# Schematics.net
KiCad netlist of a schematic drawn in Altium Designer
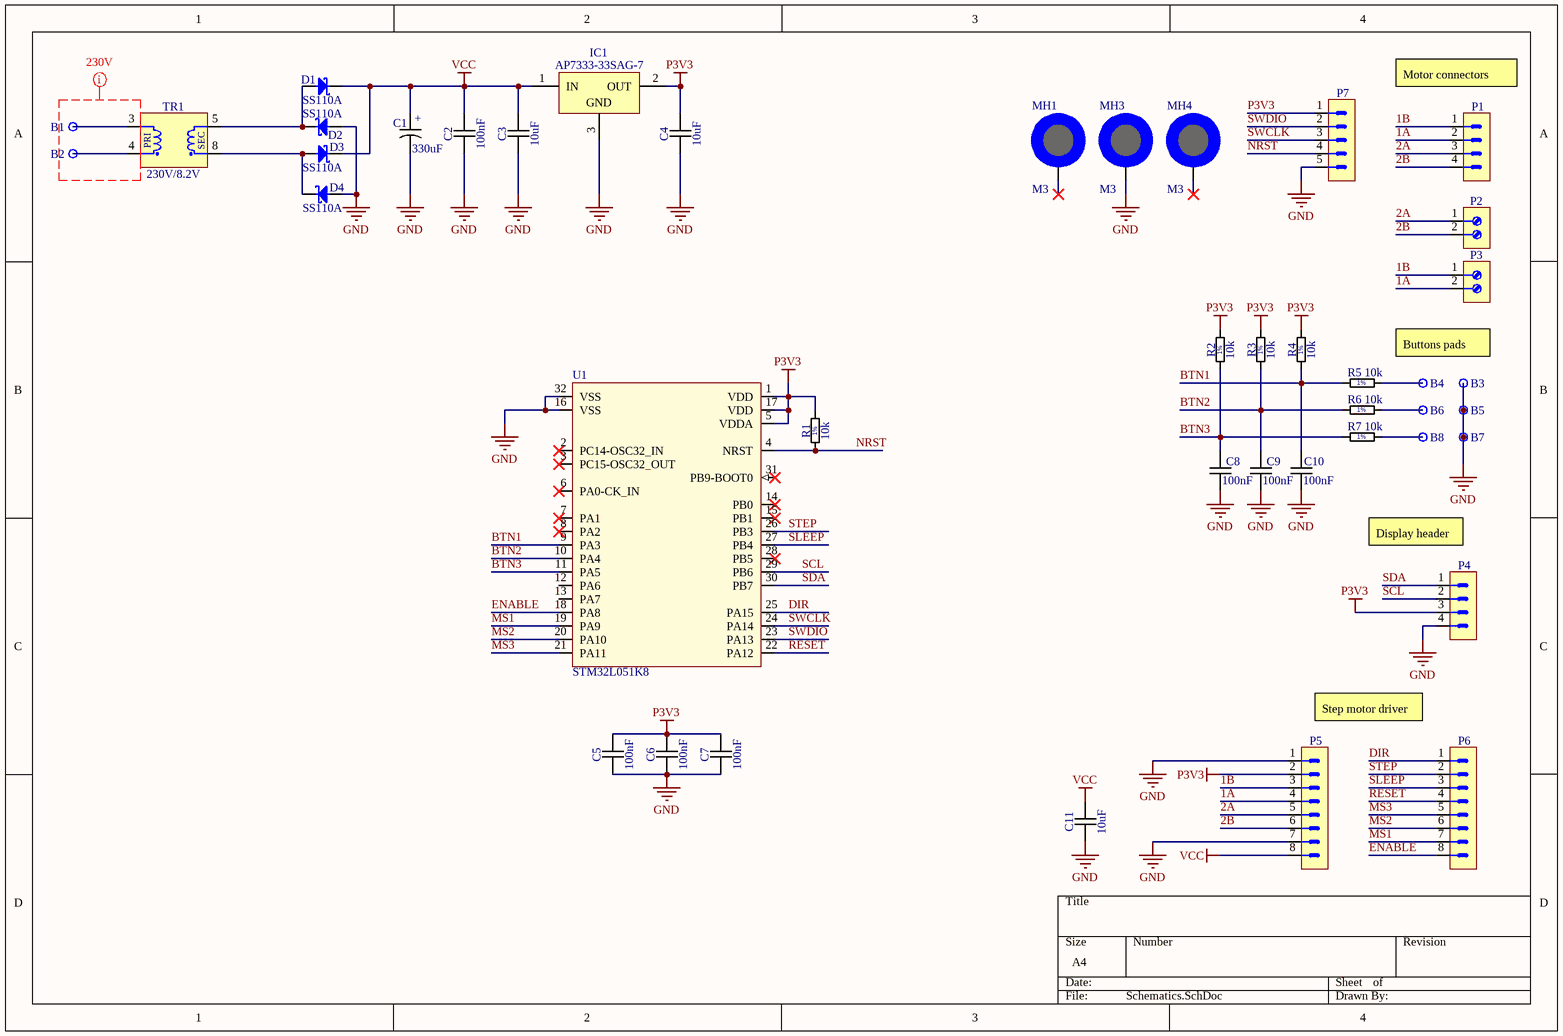
[diagram p0: Schematics.SchDoc]

(export (version "E")
  (design (tool "Eeschema 10.0.6"))
  (components
    (comp (ref "B1")
      (value "Pad")
      (footprint "PAD_THD_C350H200MM")
      (description "Plated Through Hole: Hole Dia.=2mm Pad Dia.=3.5mm")
      (fields (field (name "AUTHOR") "KB"))
      (libsource (lib "Mechanical And PCB Features") (part "THD Pad"))
    )
    (comp (ref "B2")
      (value "Pad")
      (footprint "PAD_THD_C350H200MM")
      (description "Plated Through Hole: Hole Dia.=2mm Pad Dia.=3.5mm")
      (fields (field (name "AUTHOR") "KB"))
      (libsource (lib "Mechanical And PCB Features") (part "THD Pad"))
    )
    (comp (ref "B3")
      (value "Pad")
      (footprint "PAD_THD_C150H100MM")
      (description "Plated Through Hole: Hole Dia.=1mm Pad Dia.=1.5mm")
      (fields (field (name "AUTHOR") "KB"))
      (libsource (lib "Mechanical And PCB Features") (part "THD Pad"))
    )
    (comp (ref "B4")
      (value "Pad")
      (footprint "PAD_THD_C150H100MM")
      (description "Plated Through Hole: Hole Dia.=1mm Pad Dia.=1.5mm")
      (fields (field (name "AUTHOR") "KB"))
      (libsource (lib "Mechanical And PCB Features") (part "THD Pad"))
    )
    (comp (ref "B5")
      (value "Pad")
      (footprint "PAD_THD_C150H100MM")
      (description "Plated Through Hole: Hole Dia.=1mm Pad Dia.=1.5mm")
      (fields (field (name "AUTHOR") "KB"))
      (libsource (lib "Mechanical And PCB Features") (part "THD Pad"))
    )
    (comp (ref "B6")
      (value "Pad")
      (footprint "PAD_THD_C150H100MM")
      (description "Plated Through Hole: Hole Dia.=1mm Pad Dia.=1.5mm")
      (fields (field (name "AUTHOR") "KB"))
      (libsource (lib "Mechanical And PCB Features") (part "THD Pad"))
    )
    (comp (ref "B7")
      (value "Pad")
      (footprint "PAD_THD_C150H100MM")
      (description "Plated Through Hole: Hole Dia.=1mm Pad Dia.=1.5mm")
      (fields (field (name "AUTHOR") "KB"))
      (libsource (lib "Mechanical And PCB Features") (part "THD Pad"))
    )
    (comp (ref "B8")
      (value "Pad")
      (footprint "PAD_THD_C150H100MM")
      (description "Plated Through Hole: Hole Dia.=1mm Pad Dia.=1.5mm")
      (fields (field (name "AUTHOR") "KB"))
      (libsource (lib "Mechanical And PCB Features") (part "THD Pad"))
    )
    (comp (ref "C1")
      (value "330uF")
      (footprint "CAPPR5-10x16")
      (description "Polarised capacitor")
      (fields
        (field (name "MANUFACTURER") "GENERIC")
        (field (name "MANUFACTURER PART NUMBER") "CE_THT_5-10X16_330UF_50V_20%")
        (field (name "AUTHOR") "UN")
      )
      (libsource (lib "Capacitors") (part "Capacitor - polarized"))
    )
    (comp (ref "C2")
      (value "100nF")
      (footprint "CAPC0603X90N")
      (description "Non-polarised capacitor")
      (fields
        (field (name "MANUFACTURER") "GENERIC")
        (field (name "MANUFACTURER PART NUMBER") "CC0603_100NF_16V_10%_X7R")
        (field (name "AUTHOR") "KB")
      )
      (libsource (lib "Capacitors") (part "Capacitor - non polarized"))
    )
    (comp (ref "C3")
      (value "10uF")
      (footprint "CAPC0603X90N")
      (description "Non-polarised capacitor")
      (fields
        (field (name "MANUFACTURER") "GENERIC")
        (field (name "MANUFACTURER PART NUMBER") "CC0603_10UF_16V_20%_X5R")
        (field (name "AUTHOR") "KB")
      )
      (libsource (lib "Capacitors") (part "Capacitor - non polarized"))
    )
    (comp (ref "C4")
      (value "10uF")
      (footprint "CAPC0603X90N")
      (description "Non-polarised capacitor")
      (fields
        (field (name "MANUFACTURER") "GENERIC")
        (field (name "MANUFACTURER PART NUMBER") "CC0603_10UF_16V_20%_X5R")
        (field (name "AUTHOR") "KB")
      )
      (libsource (lib "Capacitors") (part "Capacitor - non polarized"))
    )
    (comp (ref "C5")
      (value "100nF")
      (footprint "CAPC0603X90N")
      (description "Non-polarised capacitor")
      (fields
        (field (name "MANUFACTURER") "GENERIC")
        (field (name "MANUFACTURER PART NUMBER") "CC0603_100NF_16V_10%_X7R")
        (field (name "AUTHOR") "KB")
      )
      (libsource (lib "Capacitors") (part "Capacitor - non polarized"))
    )
    (comp (ref "C6")
      (value "100nF")
      (footprint "CAPC0603X90N")
      (description "Non-polarised capacitor")
      (fields
        (field (name "MANUFACTURER") "GENERIC")
        (field (name "MANUFACTURER PART NUMBER") "CC0603_100NF_16V_10%_X7R")
        (field (name "AUTHOR") "KB")
      )
      (libsource (lib "Capacitors") (part "Capacitor - non polarized"))
    )
    (comp (ref "C7")
      (value "100nF")
      (footprint "CAPC0603X90N")
      (description "Non-polarised capacitor")
      (fields
        (field (name "MANUFACTURER") "GENERIC")
        (field (name "MANUFACTURER PART NUMBER") "CC0603_100NF_16V_10%_X7R")
        (field (name "AUTHOR") "KB")
      )
      (libsource (lib "Capacitors") (part "Capacitor - non polarized"))
    )
    (comp (ref "C8")
      (value "100nF")
      (footprint "CAPC0603X90N")
      (description "Non-polarised capacitor")
      (fields
        (field (name "MANUFACTURER") "GENERIC")
        (field (name "MANUFACTURER PART NUMBER") "CC0603_100NF_16V_10%_X7R")
        (field (name "AUTHOR") "KB")
      )
      (libsource (lib "Capacitors") (part "Capacitor - non polarized"))
    )
    (comp (ref "C9")
      (value "100nF")
      (footprint "CAPC0603X90N")
      (description "Non-polarised capacitor")
      (fields
        (field (name "MANUFACTURER") "GENERIC")
        (field (name "MANUFACTURER PART NUMBER") "CC0603_100NF_16V_10%_X7R")
        (field (name "AUTHOR") "KB")
      )
      (libsource (lib "Capacitors") (part "Capacitor - non polarized"))
    )
    (comp (ref "C10")
      (value "100nF")
      (footprint "CAPC0603X90N")
      (description "Non-polarised capacitor")
      (fields
        (field (name "MANUFACTURER") "GENERIC")
        (field (name "MANUFACTURER PART NUMBER") "CC0603_100NF_16V_10%_X7R")
        (field (name "AUTHOR") "KB")
      )
      (libsource (lib "Capacitors") (part "Capacitor - non polarized"))
    )
    (comp (ref "C11")
      (value "10uF")
      (footprint "CAPC0603X90N")
      (description "Non-polarised capacitor")
      (fields
        (field (name "MANUFACTURER") "GENERIC")
        (field (name "MANUFACTURER PART NUMBER") "CC0603_10UF_16V_20%_X5R")
        (field (name "AUTHOR") "KB")
      )
      (libsource (lib "Capacitors") (part "Capacitor - non polarized"))
    )
    (comp (ref "D1")
      (value "SS110A")
      (footprint "DO-214AC - Schottky")
      (description "Surface Mount Schottky Rectifier")
      (fields (field (name "AUTHOR") "JK"))
      (libsource (lib "ICs And Semiconductors") (part "Diode Schottky"))
    )
    (comp (ref "D2")
      (value "SS110A")
      (footprint "DO-214AC - Schottky")
      (description "Surface Mount Schottky Rectifier")
      (fields (field (name "AUTHOR") "JK"))
      (libsource (lib "ICs And Semiconductors") (part "Diode Schottky"))
    )
    (comp (ref "D3")
      (value "SS110A")
      (footprint "DO-214AC - Schottky")
      (description "Surface Mount Schottky Rectifier")
      (fields (field (name "AUTHOR") "JK"))
      (libsource (lib "ICs And Semiconductors") (part "Diode Schottky"))
    )
    (comp (ref "D4")
      (value "SS110A")
      (footprint "DO-214AC - Schottky")
      (description "Surface Mount Schottky Rectifier")
      (fields (field (name "AUTHOR") "JK"))
      (libsource (lib "ICs And Semiconductors") (part "Diode Schottky"))
    )
    (comp (ref "IC1")
      (value "AP7333-33SAG-7")
      (footprint "SOT23-3")
      (description "3.3V, 0.3A output; Vin 6V max, 0.3V dropout")
      (fields (field (name "AUTHOR") "BS"))
      (libsource (lib "ICs And Semiconductors") (part "REG3 1IN-2OUT-3GND"))
    )
    (comp (ref "MH1")
      (value "M3")
      (footprint "MH-M3_COPPER_WASHER")
      (description "Mounting hole, M3, exposed pad, space for washer")
      (fields (field (name "AUTHOR") "KB"))
      (libsource (lib "Mechanical And PCB Features") (part "MH"))
    )
    (comp (ref "MH3")
      (value "M3")
      (footprint "MH-M3_COPPER_WASHER")
      (description "Mounting hole, M3, exposed pad, space for washer")
      (fields (field (name "AUTHOR") "KB"))
      (libsource (lib "Mechanical And PCB Features") (part "MH"))
    )
    (comp (ref "MH4")
      (value "M3")
      (footprint "MH-M3_COPPER_WASHER")
      (description "Mounting hole, M3, exposed pad, space for washer")
      (fields (field (name "AUTHOR") "KB"))
      (libsource (lib "Mechanical And PCB Features") (part "MH"))
    )
    (comp (ref "P1")
      (value "B4B-PH-K-S")
      (footprint "B4B-PH-K-S")
      (description "2mm header socket, vertical, 4 Positions, THT, 9.9x4.5mm body")
      (fields (field (name "MANUFACTURER") "GENERIC") (field (name "AUTHOR") "KB"))
      (libsource (lib "Connectors") (part "Header 4x1"))
    )
    (comp (ref "P2")
      (value "1776275")
      (footprint "SCREWERM_THT_2X1H_3P5MM")
      (description "Terminal Block, Right angle, 2 Positions, THT, Screw Connection, 7x7mm body")
      (fields
        (field (name "MANUFACTURER") "GENERIC")
        (field (name "MANUFACTURER PART NUMBER") "SCREWERM_THT_2X1H_3P5MM")
        (field (name "AUTHOR") "JK")
      )
      (libsource (lib "Connectors") (part "Terminal Block_2 Positions_Screw Connection"))
    )
    (comp (ref "P3")
      (value "1776275")
      (footprint "SCREWERM_THT_2X1H_3P5MM")
      (description "Terminal Block, Right angle, 2 Positions, THT, Screw Connection, 7x7mm body")
      (fields
        (field (name "MANUFACTURER") "GENERIC")
        (field (name "MANUFACTURER PART NUMBER") "SCREWERM_THT_2X1H_3P5MM")
        (field (name "AUTHOR") "JK")
      )
      (libsource (lib "Connectors") (part "Terminal Block_2 Positions_Screw Connection"))
    )
    (comp (ref "P4")
      (value "SSW-104-02-L-S")
      (footprint "SAMTEC_SSW-104-02-L-S")
      (description "General Purpose Header: THT, 2.54mm, Female, Straight")
      (fields
        (field (name "MANUFACTURER") "GENERIC")
        (field (name "MANUFACTURER PART NUMBER") "HDR_THT_4X1V_F_2P54MM")
        (field (name "AUTHOR") "PC")
      )
      (libsource (lib "Connectors") (part "Header 4x1"))
    )
    (comp (ref "P5")
      (value "68000-208HLF")
      (footprint "Header_8x1_V_2.54mm_M")
      (description "General Purpose Header: THT, 2.54mm, Male, Straight")
      (fields
        (field (name "MANUFACTURER") "GENERIC")
        (field (name "MANUFACTURER PART NUMBER") "Header_8x1_V_2.54mm_M")
        (field (name "AUTHOR") "JK")
      )
      (libsource (lib "Connectors") (part "Header 8x1"))
    )
    (comp (ref "P6")
      (value "68000-208HLF")
      (footprint "Header_8x1_V_2.54mm_M")
      (description "General Purpose Header: THT, 2.54mm, Male, Straight")
      (fields
        (field (name "MANUFACTURER") "GENERIC")
        (field (name "MANUFACTURER PART NUMBER") "Header_8x1_V_2.54mm_M")
        (field (name "AUTHOR") "JK")
      )
      (libsource (lib "Connectors") (part "Header 8x1"))
    )
    (comp (ref "P7")
      (value "SSW-105-02-G-S")
      (footprint "SAMTEC_SSW-105-02-G-S")
      (description "General Purpose Header: THT, 2.54mm, Female, Straight, Long Lead")
      (fields
        (field (name "MANUFACTURER") "GENERIC")
        (field (name "MANUFACTURER PART NUMBER") "HDR_THT_5X1V_F_2P54MM")
        (field (name "AUTHOR") "UN")
      )
      (libsource (lib "Connectors") (part "Header 5x1"))
    )
    (comp (ref "R1")
      (value "10k")
      (footprint "RESC0603X60N")
      (description "General Purpose Thick Film Chip Resistor")
      (fields
        (field (name "MANUFACTURER") "GENERIC")
        (field (name "MANUFACTURER PART NUMBER") "R0603_10K0_0.0625W 0.1W 0.125W 0.25W 0.5W 1W 0.75W 1W_100PPM")
        (field (name "AUTHOR") "KB")
      )
      (libsource (lib "Resistors") (part "Resistor - 1%"))
    )
    (comp (ref "R2")
      (value "10k")
      (footprint "RESC0603X60N")
      (description "General Purpose Thick Film Chip Resistor")
      (fields
        (field (name "MANUFACTURER") "GENERIC")
        (field (name "MANUFACTURER PART NUMBER") "R0603_10K0_0.0625W 0.1W 0.125W 0.25W 0.5W 1W 0.75W 1W_100PPM")
        (field (name "AUTHOR") "KB")
      )
      (libsource (lib "Resistors") (part "Resistor - 1%"))
    )
    (comp (ref "R3")
      (value "10k")
      (footprint "RESC0603X60N")
      (description "General Purpose Thick Film Chip Resistor")
      (fields
        (field (name "MANUFACTURER") "GENERIC")
        (field (name "MANUFACTURER PART NUMBER") "R0603_10K0_0.0625W 0.1W 0.125W 0.25W 0.5W 1W 0.75W 1W_100PPM")
        (field (name "AUTHOR") "KB")
      )
      (libsource (lib "Resistors") (part "Resistor - 1%"))
    )
    (comp (ref "R4")
      (value "10k")
      (footprint "RESC0603X60N")
      (description "General Purpose Thick Film Chip Resistor")
      (fields
        (field (name "MANUFACTURER") "GENERIC")
        (field (name "MANUFACTURER PART NUMBER") "R0603_10K0_0.0625W 0.1W 0.125W 0.25W 0.5W 1W 0.75W 1W_100PPM")
        (field (name "AUTHOR") "KB")
      )
      (libsource (lib "Resistors") (part "Resistor - 1%"))
    )
    (comp (ref "R5")
      (value "10k")
      (footprint "RESC0603X60N")
      (description "General Purpose Thick Film Chip Resistor")
      (fields
        (field (name "MANUFACTURER") "GENERIC")
        (field (name "MANUFACTURER PART NUMBER") "R0603_10K0_0.0625W 0.1W 0.125W 0.25W 0.5W 1W 0.75W 1W_100PPM")
        (field (name "AUTHOR") "KB")
      )
      (libsource (lib "Resistors") (part "Resistor - 1%"))
    )
    (comp (ref "R6")
      (value "10k")
      (footprint "RESC0603X60N")
      (description "General Purpose Thick Film Chip Resistor")
      (fields
        (field (name "MANUFACTURER") "GENERIC")
        (field (name "MANUFACTURER PART NUMBER") "R0603_10K0_0.0625W 0.1W 0.125W 0.25W 0.5W 1W 0.75W 1W_100PPM")
        (field (name "AUTHOR") "KB")
      )
      (libsource (lib "Resistors") (part "Resistor - 1%"))
    )
    (comp (ref "R7")
      (value "10k")
      (footprint "RESC0603X60N")
      (description "General Purpose Thick Film Chip Resistor")
      (fields
        (field (name "MANUFACTURER") "GENERIC")
        (field (name "MANUFACTURER PART NUMBER") "R0603_10K0_0.0625W 0.1W 0.125W 0.25W 0.5W 1W 0.75W 1W_100PPM")
        (field (name "AUTHOR") "KB")
      )
      (libsource (lib "Resistors") (part "Resistor - 1%"))
    )
    (comp (ref "TR1")
      (value "230V/8.2V")
      (footprint "TS 2/14")
      (description "Transformer")
      (fields
        (field (name "MANUFACTURER") "INDEL")
        (field (name "MANUFACTURER PART NUMBER") "TS 2/14")
        (field (name "AUTHOR") "JK")
      )
      (libsource (lib "Inductors") (part "TS 2/14"))
    )
    (comp (ref "U1")
      (value "STM32L051K8")
      (footprint "STM-LQFP32_N")
      (description "Ultra-low-power ARM Cortex-M0+ MCU with 64 Kbytes Flash, 32 MHz CPU")
      (fields (field (name "MANUFACTURER 1 PART NUMBER") "STM32L051K8T6") (field (name "AUTHOR") "JK"))
      (libsource (lib "ICs And Semiconductors") (part "STM32L051K8"))
    )
  )
  (nets
    (net (code "1") (name "/1A") (class "Default")
      (node (ref "P1") (pin "2") (pinfunction "2_2") (pintype "passive"))
      (node (ref "P3") (pin "2") (pinfunction "2_2") (pintype "passive"))
      (node (ref "P5") (pin "4") (pinfunction "4_4") (pintype "passive"))
    )
    (net (code "2") (name "/1B") (class "Default")
      (node (ref "P1") (pin "1") (pinfunction "1_1") (pintype "passive"))
      (node (ref "P3") (pin "1") (pinfunction "1_1") (pintype "passive"))
      (node (ref "P5") (pin "3") (pinfunction "3_3") (pintype "passive"))
    )
    (net (code "3") (name "/2A") (class "Default")
      (node (ref "P1") (pin "3") (pinfunction "3_3") (pintype "passive"))
      (node (ref "P2") (pin "1") (pinfunction "1_1") (pintype "passive"))
      (node (ref "P5") (pin "5") (pinfunction "5_5") (pintype "passive"))
    )
    (net (code "4") (name "/2B") (class "Default")
      (node (ref "P1") (pin "4") (pinfunction "4_4") (pintype "passive"))
      (node (ref "P2") (pin "2") (pinfunction "2_2") (pintype "passive"))
      (node (ref "P5") (pin "6") (pinfunction "6_6") (pintype "passive"))
    )
    (net (code "5") (name "/BTN1") (class "Default")
      (node (ref "C10") (pin "2") (pinfunction "2_2") (pintype "passive"))
      (node (ref "R4") (pin "1") (pinfunction "1_1") (pintype "passive"))
      (node (ref "R5") (pin "1") (pinfunction "1_1") (pintype "passive"))
      (node (ref "U1") (pin "9") (pinfunction "PA3_9") (pintype "bidirectional"))
    )
    (net (code "6") (name "/BTN2") (class "Default")
      (node (ref "C9") (pin "2") (pinfunction "2_2") (pintype "passive"))
      (node (ref "R3") (pin "1") (pinfunction "1_1") (pintype "passive"))
      (node (ref "R6") (pin "1") (pinfunction "1_1") (pintype "passive"))
      (node (ref "U1") (pin "10") (pinfunction "PA4_10") (pintype "bidirectional"))
    )
    (net (code "7") (name "/BTN3") (class "Default")
      (node (ref "C8") (pin "2") (pinfunction "2_2") (pintype "passive"))
      (node (ref "R2") (pin "1") (pinfunction "1_1") (pintype "passive"))
      (node (ref "R7") (pin "1") (pinfunction "1_1") (pintype "passive"))
      (node (ref "U1") (pin "11") (pinfunction "PA5_11") (pintype "bidirectional"))
    )
    (net (code "8") (name "/DIR") (class "Default")
      (node (ref "P6") (pin "1") (pinfunction "1_1") (pintype "passive"))
      (node (ref "U1") (pin "25") (pinfunction "PA15_25") (pintype "bidirectional"))
    )
    (net (code "9") (name "/ENABLE") (class "Default")
      (node (ref "P6") (pin "8") (pinfunction "8_8") (pintype "passive"))
      (node (ref "U1") (pin "18") (pinfunction "PA8_18") (pintype "bidirectional"))
    )
    (net (code "10") (name "/MS1") (class "Default")
      (node (ref "P6") (pin "7") (pinfunction "7_7") (pintype "passive"))
      (node (ref "U1") (pin "19") (pinfunction "PA9_19") (pintype "bidirectional"))
    )
    (net (code "11") (name "/MS2") (class "Default")
      (node (ref "P6") (pin "6") (pinfunction "6_6") (pintype "passive"))
      (node (ref "U1") (pin "20") (pinfunction "PA10_20") (pintype "bidirectional"))
    )
    (net (code "12") (name "/MS3") (class "Default")
      (node (ref "P6") (pin "5") (pinfunction "5_5") (pintype "passive"))
      (node (ref "U1") (pin "21") (pinfunction "PA11_21") (pintype "bidirectional"))
    )
    (net (code "13") (name "/NRST") (class "Default")
      (node (ref "P7") (pin "4") (pinfunction "4_4") (pintype "passive"))
      (node (ref "R1") (pin "1") (pinfunction "1_1") (pintype "passive"))
      (node (ref "U1") (pin "4") (pinfunction "NRST_4") (pintype "bidirectional"))
    )
    (net (code "14") (name "/RESET") (class "Default")
      (node (ref "P6") (pin "4") (pinfunction "4_4") (pintype "passive"))
      (node (ref "U1") (pin "22") (pinfunction "PA12_22") (pintype "bidirectional"))
    )
    (net (code "15") (name "/SCL") (class "Default")
      (node (ref "P4") (pin "2") (pinfunction "2_2") (pintype "passive"))
      (node (ref "U1") (pin "29") (pinfunction "PB6_29") (pintype "bidirectional"))
    )
    (net (code "16") (name "/SDA") (class "Default")
      (node (ref "P4") (pin "1") (pinfunction "1_1") (pintype "passive"))
      (node (ref "U1") (pin "30") (pinfunction "PB7_30") (pintype "bidirectional"))
    )
    (net (code "17") (name "/SLEEP") (class "Default")
      (node (ref "P6") (pin "3") (pinfunction "3_3") (pintype "passive"))
      (node (ref "U1") (pin "27") (pinfunction "PB4_27") (pintype "bidirectional"))
    )
    (net (code "18") (name "/STEP") (class "Default")
      (node (ref "P6") (pin "2") (pinfunction "2_2") (pintype "passive"))
      (node (ref "U1") (pin "26") (pinfunction "PB3_26") (pintype "bidirectional"))
    )
    (net (code "19") (name "/SWCLK") (class "Default")
      (node (ref "P7") (pin "3") (pinfunction "3_3") (pintype "passive"))
      (node (ref "U1") (pin "24") (pinfunction "PA14_24") (pintype "bidirectional"))
    )
    (net (code "20") (name "/SWDIO") (class "Default")
      (node (ref "P7") (pin "2") (pinfunction "2_2") (pintype "passive"))
      (node (ref "U1") (pin "23") (pinfunction "PA13_23") (pintype "bidirectional"))
    )
    (net (code "21") (name "GND") (class "Default")
      (node (ref "B3") (pin "1") (pinfunction "1_1") (pintype "bidirectional"))
      (node (ref "B5") (pin "1") (pinfunction "1_1") (pintype "bidirectional"))
      (node (ref "B7") (pin "1") (pinfunction "1_1") (pintype "bidirectional"))
      (node (ref "C1") (pin "2") (pinfunction "2_2") (pintype "passive"))
      (node (ref "C10") (pin "1") (pinfunction "1_1") (pintype "passive"))
      (node (ref "C11") (pin "1") (pinfunction "1_1") (pintype "passive"))
      (node (ref "C2") (pin "1") (pinfunction "1_1") (pintype "passive"))
      (node (ref "C3") (pin "1") (pinfunction "1_1") (pintype "passive"))
      (node (ref "C4") (pin "1") (pinfunction "1_1") (pintype "passive"))
      (node (ref "C5") (pin "1") (pinfunction "1_1") (pintype "passive"))
      (node (ref "C6") (pin "1") (pinfunction "1_1") (pintype "passive"))
      (node (ref "C7") (pin "1") (pinfunction "1_1") (pintype "passive"))
      (node (ref "C8") (pin "1") (pinfunction "1_1") (pintype "passive"))
      (node (ref "C9") (pin "1") (pinfunction "1_1") (pintype "passive"))
      (node (ref "D2") (pin "2") (pinfunction "A_2") (pintype "passive"))
      (node (ref "D4") (pin "2") (pinfunction "A_2") (pintype "passive"))
      (node (ref "IC1") (pin "3") (pinfunction "GND_3") (pintype "power_in"))
      (node (ref "MH3") (pin "MH") (pinfunction "MH_MH") (pintype "passive"))
      (node (ref "P4") (pin "4") (pinfunction "4_4") (pintype "passive"))
      (node (ref "P5") (pin "1") (pinfunction "1_1") (pintype "passive"))
      (node (ref "P5") (pin "7") (pinfunction "7_7") (pintype "passive"))
      (node (ref "P7") (pin "5") (pinfunction "5_5") (pintype "passive"))
      (node (ref "U1") (pin "16") (pinfunction "VSS_16") (pintype "power_in"))
      (node (ref "U1") (pin "32") (pinfunction "VSS_32") (pintype "power_in"))
    )
    (net (code "22") (name "Net-(B1-Pad1)") (class "Default")
      (node (ref "B1") (pin "1") (pinfunction "1_1") (pintype "bidirectional"))
      (node (ref "TR1") (pin "3") (pinfunction "3_3") (pintype "passive"))
    )
    (net (code "23") (name "Net-(B2-Pad1)") (class "Default")
      (node (ref "B2") (pin "1") (pinfunction "1_1") (pintype "bidirectional"))
      (node (ref "TR1") (pin "4") (pinfunction "4_4") (pintype "passive"))
    )
    (net (code "24") (name "Net-(B4-Pad1)") (class "Default")
      (node (ref "B4") (pin "1") (pinfunction "1_1") (pintype "bidirectional"))
      (node (ref "R5") (pin "2") (pinfunction "2_2") (pintype "passive"))
    )
    (net (code "25") (name "Net-(B6-Pad1)") (class "Default")
      (node (ref "B6") (pin "1") (pinfunction "1_1") (pintype "bidirectional"))
      (node (ref "R6") (pin "2") (pinfunction "2_2") (pintype "passive"))
    )
    (net (code "26") (name "Net-(B8-Pad1)") (class "Default")
      (node (ref "B8") (pin "1") (pinfunction "1_1") (pintype "bidirectional"))
      (node (ref "R7") (pin "2") (pinfunction "2_2") (pintype "passive"))
    )
    (net (code "27") (name "Net-(D1-A)") (class "Default")
      (node (ref "D1") (pin "2") (pinfunction "A_2") (pintype "passive"))
      (node (ref "D2") (pin "1") (pinfunction "C_1") (pintype "passive"))
      (node (ref "TR1") (pin "5") (pinfunction "5_5") (pintype "passive"))
    )
    (net (code "28") (name "Net-(D3-A)") (class "Default")
      (node (ref "D3") (pin "2") (pinfunction "A_2") (pintype "passive"))
      (node (ref "D4") (pin "1") (pinfunction "C_1") (pintype "passive"))
      (node (ref "TR1") (pin "8") (pinfunction "8_8") (pintype "passive"))
    )
    (net (code "29") (name "P3V3") (class "Default")
      (node (ref "C4") (pin "2") (pinfunction "2_2") (pintype "passive"))
      (node (ref "C5") (pin "2") (pinfunction "2_2") (pintype "passive"))
      (node (ref "C6") (pin "2") (pinfunction "2_2") (pintype "passive"))
      (node (ref "C7") (pin "2") (pinfunction "2_2") (pintype "passive"))
      (node (ref "IC1") (pin "2") (pinfunction "OUT_2") (pintype "power_in"))
      (node (ref "P4") (pin "3") (pinfunction "3_3") (pintype "passive"))
      (node (ref "P5") (pin "2") (pinfunction "2_2") (pintype "passive"))
      (node (ref "P7") (pin "1") (pinfunction "1_1") (pintype "passive"))
      (node (ref "R1") (pin "2") (pinfunction "2_2") (pintype "passive"))
      (node (ref "R2") (pin "2") (pinfunction "2_2") (pintype "passive"))
      (node (ref "R3") (pin "2") (pinfunction "2_2") (pintype "passive"))
      (node (ref "R4") (pin "2") (pinfunction "2_2") (pintype "passive"))
      (node (ref "U1") (pin "1") (pinfunction "VDD_1") (pintype "power_in"))
      (node (ref "U1") (pin "17") (pinfunction "VDD_17") (pintype "power_in"))
      (node (ref "U1") (pin "5") (pinfunction "VDDA_5") (pintype "power_in"))
    )
    (net (code "30") (name "VCC") (class "Default")
      (node (ref "C1") (pin "1") (pinfunction "1_1") (pintype "passive"))
      (node (ref "C11") (pin "2") (pinfunction "2_2") (pintype "passive"))
      (node (ref "C2") (pin "2") (pinfunction "2_2") (pintype "passive"))
      (node (ref "C3") (pin "2") (pinfunction "2_2") (pintype "passive"))
      (node (ref "D1") (pin "1") (pinfunction "C_1") (pintype "passive"))
      (node (ref "D3") (pin "1") (pinfunction "C_1") (pintype "passive"))
      (node (ref "IC1") (pin "1") (pinfunction "IN_1") (pintype "power_in"))
      (node (ref "P5") (pin "8") (pinfunction "8_8") (pintype "passive"))
    )
    (net (code "31") (name "unconnected-(MH1-PadMH)") (class "Default")
      (node (ref "MH1") (pin "MH") (pinfunction "MH_MH") (pintype "passive+no_connect"))
    )
    (net (code "32") (name "unconnected-(MH4-PadMH)") (class "Default")
      (node (ref "MH4") (pin "MH") (pinfunction "MH_MH") (pintype "passive+no_connect"))
    )
    (net (code "33") (name "unconnected-(U1-PA0-CK_IN-Pad6)") (class "Default")
      (node (ref "U1") (pin "6") (pinfunction "PA0-CK_IN_6") (pintype "bidirectional+no_connect"))
    )
    (net (code "34") (name "unconnected-(U1-PA1-Pad7)") (class "Default")
      (node (ref "U1") (pin "7") (pinfunction "PA1_7") (pintype "bidirectional+no_connect"))
    )
    (net (code "35") (name "unconnected-(U1-PA2-Pad8)") (class "Default")
      (node (ref "U1") (pin "8") (pinfunction "PA2_8") (pintype "bidirectional+no_connect"))
    )
    (net (code "36") (name "unconnected-(U1-PA6-Pad12)") (class "Default")
      (node (ref "U1") (pin "12") (pinfunction "PA6_12") (pintype "bidirectional"))
    )
    (net (code "37") (name "unconnected-(U1-PA7-Pad13)") (class "Default")
      (node (ref "U1") (pin "13") (pinfunction "PA7_13") (pintype "bidirectional"))
    )
    (net (code "38") (name "unconnected-(U1-PB0-Pad14)") (class "Default")
      (node (ref "U1") (pin "14") (pinfunction "PB0_14") (pintype "bidirectional+no_connect"))
    )
    (net (code "39") (name "unconnected-(U1-PB1-Pad15)") (class "Default")
      (node (ref "U1") (pin "15") (pinfunction "PB1_15") (pintype "bidirectional+no_connect"))
    )
    (net (code "40") (name "unconnected-(U1-PB5-Pad28)") (class "Default")
      (node (ref "U1") (pin "28") (pinfunction "PB5_28") (pintype "bidirectional+no_connect"))
    )
    (net (code "41") (name "unconnected-(U1-PB9-BOOT0-Pad31)") (class "Default")
      (node (ref "U1") (pin "31") (pinfunction "PB9-BOOT0_31") (pintype "input+no_connect"))
    )
    (net (code "42") (name "unconnected-(U1-PC14-OSC32_IN-Pad2)") (class "Default")
      (node (ref "U1") (pin "2") (pinfunction "PC14-OSC32_IN_2") (pintype "bidirectional+no_connect"))
    )
    (net (code "43") (name "unconnected-(U1-PC15-OSC32_OUT-Pad3)") (class "Default")
      (node (ref "U1") (pin "3") (pinfunction "PC15-OSC32_OUT_3") (pintype "bidirectional+no_connect"))
    )
  )
)
